# stv_bypass.net
KiCad netlist of a schematic drawn in Altium Designer
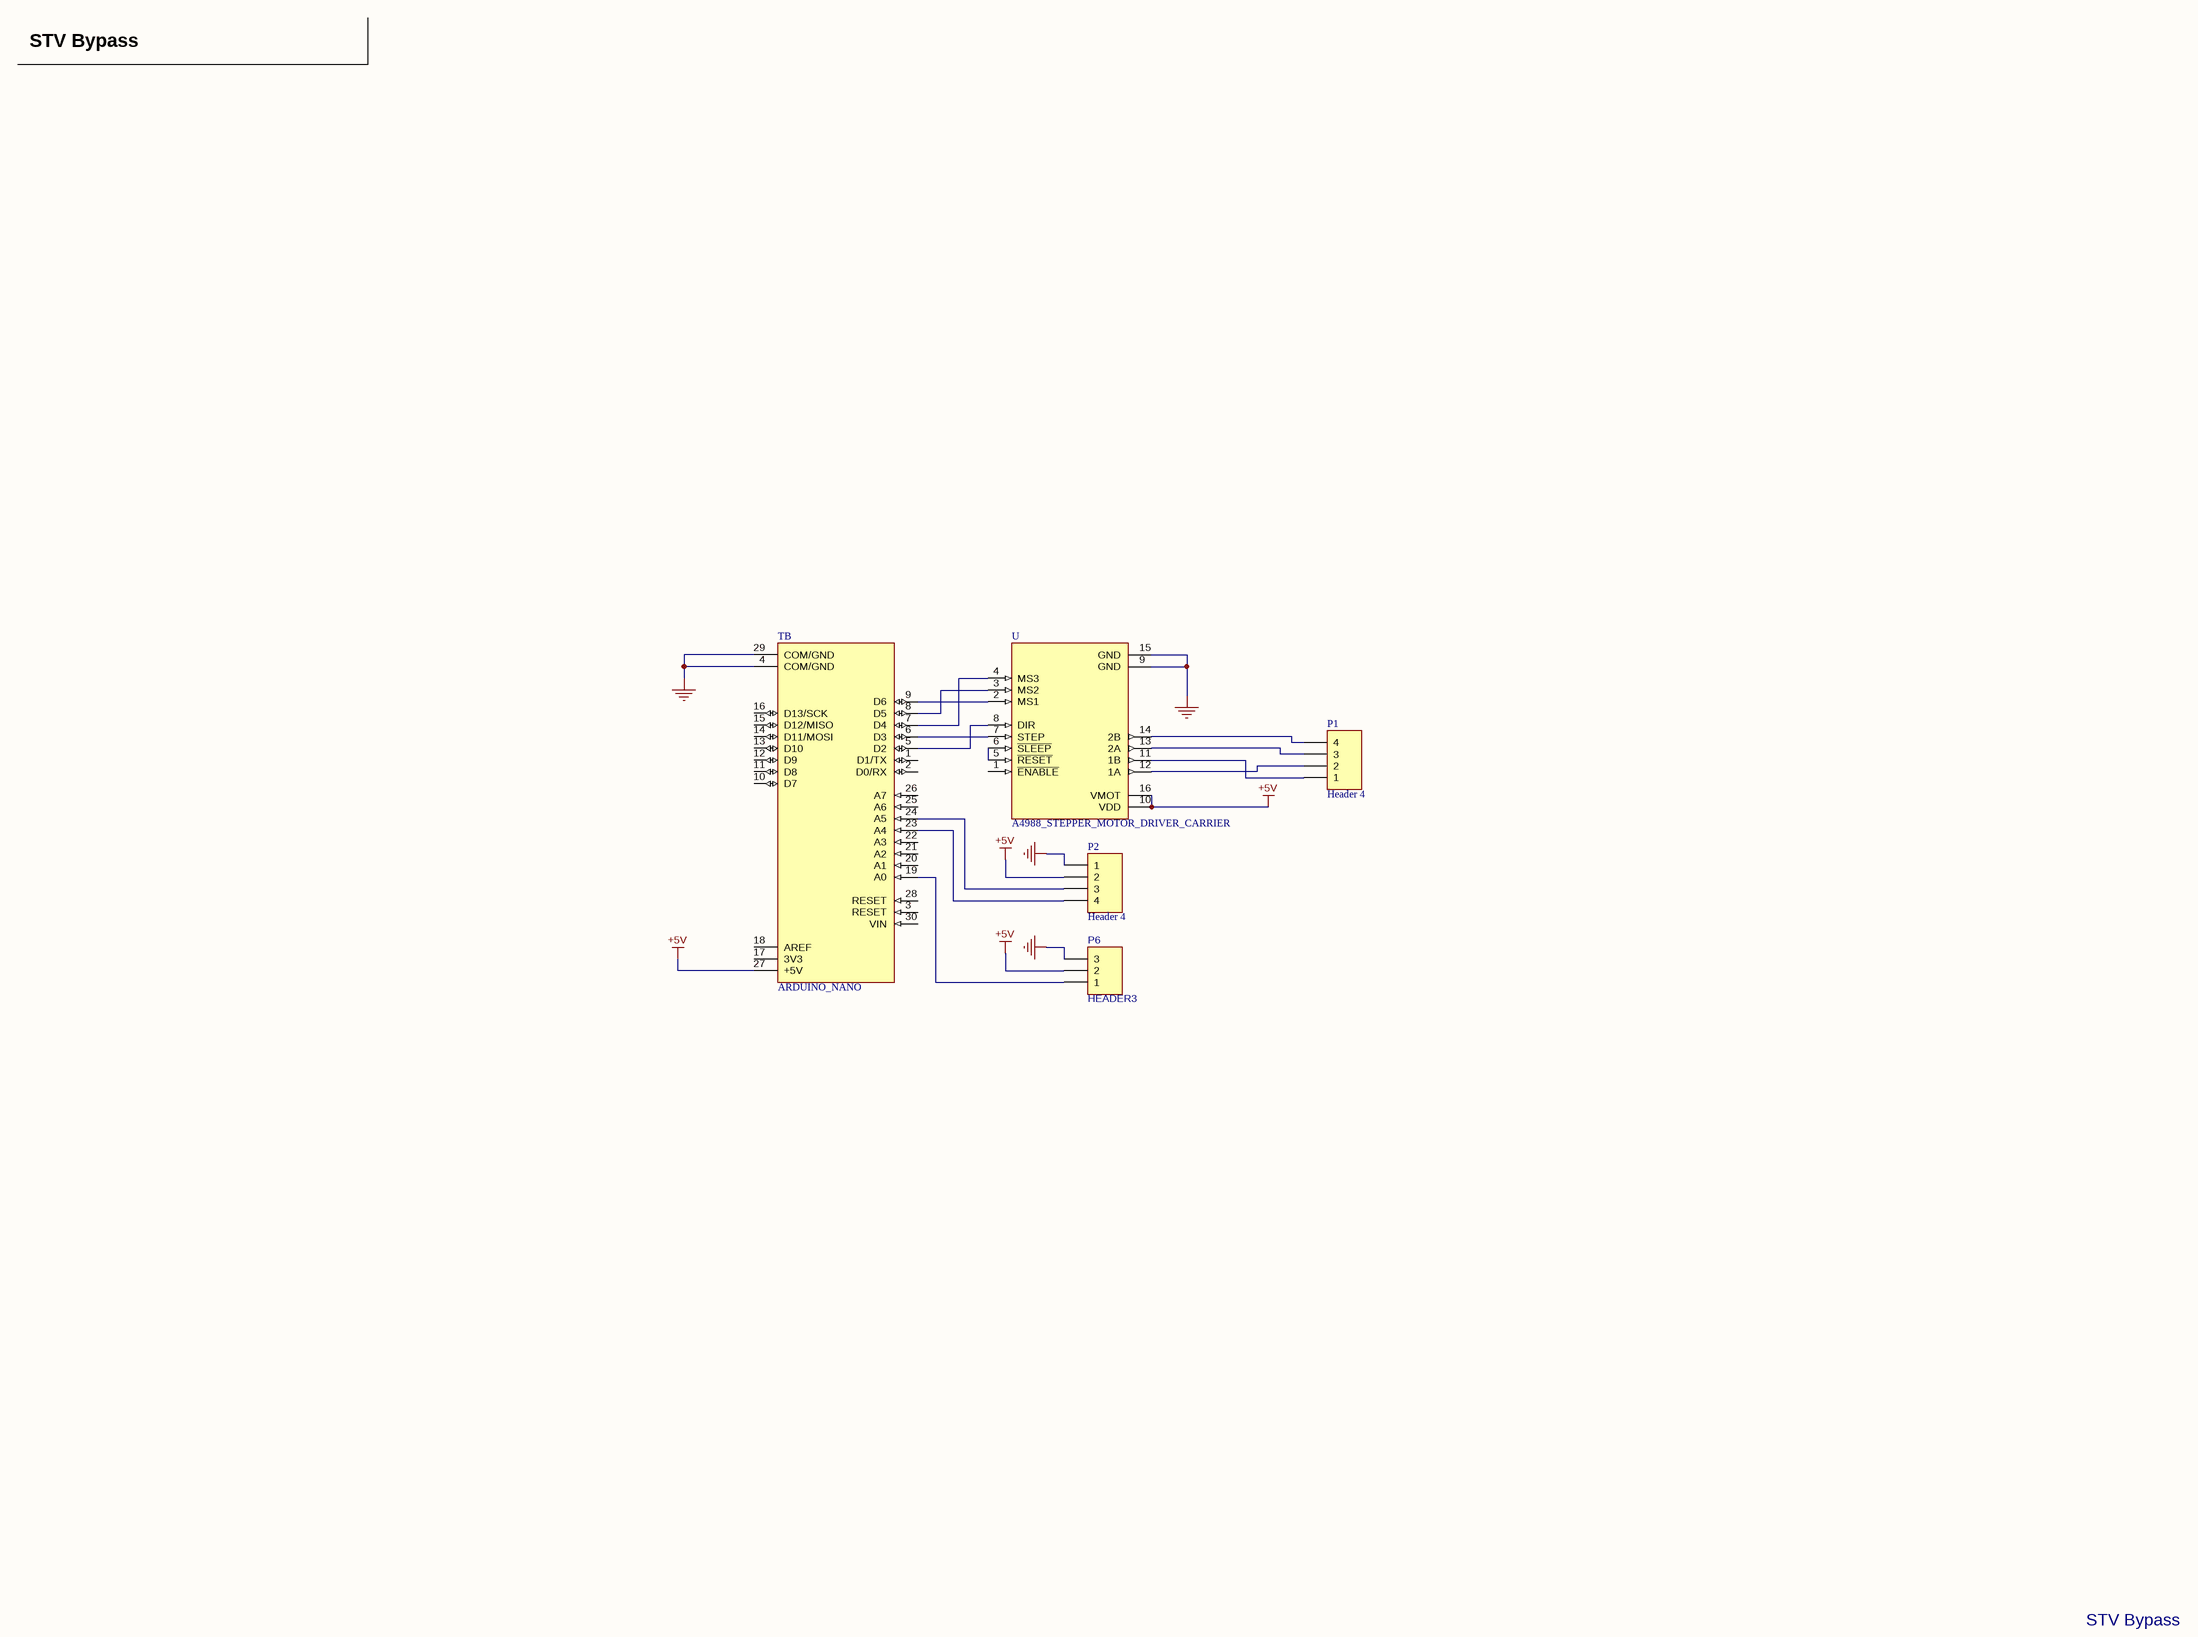
[diagram p0: stv_bypass.SchDoc]

(export (version "E")
  (design (tool "Eeschema 10.0.6"))
  (components
    (comp (ref "P1")
      (value "Header 4")
      (footprint "HDR1X4")
      (description "Header, 4-Pin")
      (fields (field (name "PUBLISHER") "Altium Limited"))
      (libsource (lib "Miscellaneous Connectors") (part "Header 4"))
    )
    (comp (ref "P2")
      (value "Header 4")
      (footprint "HDR1X4")
      (description "Header, 4-Pin")
      (fields (field (name "PUBLISHER") "Altium Limited"))
      (libsource (lib "") (part "Header 4_1"))
    )
    (comp (ref "P6")
      (value "HEADER3")
      (footprint "HDR1X3")
      (description "CONN HEADER MALE 3POS .1\" GOLD")
      (libsource (lib "silverbullet") (part "HEADER-3_1"))
    )
    (comp (ref "TB")
      (value "ARDUINO_NANO")
      (footprint "SnapEDApcb:SHIELD_ARDUINO_NANO")
      (description "ATSAMD21G18A Arduino Nano 33 IoT SAM D ARMÂ® CortexÂ®-M0+ MCU 32-Bit Embedded Evaluation Board")
      (fields (field (name "MP") "ARDUINO NANO") (field (name "MF") "Arduino"))
      (libsource (lib "SnapEDAsch") (part "ARDUINO_NANO"))
    )
    (comp (ref "U")
      (value "A4988_STEPPER_MOTOR_DRIVER_CARRIER")
      (footprint "SnapEDApcb:MODULE_A4988_STEPPER_MOTOR_DRIVER_CARRIER")
      (description "Stepper Motor Driver")
      (fields (field (name "MP") "A4988 STEPPER MOTOR DRIVER CARRIER") (field (name "MF") "Pololu"))
      (libsource (lib "SnapEDAsch") (part "A4988_STEPPER_MOTOR_DRIVER_CARRIER"))
    )
  )
  (nets
    (net (code "1") (name "+5V") (class "Default")
      (node (ref "P2") (pin "2") (pinfunction "2_2") (pintype "passive"))
      (node (ref "P6") (pin "2") (pinfunction "2_2") (pintype "passive"))
      (node (ref "TB") (pin "27") (pinfunction "+5V_27") (pintype "power_in"))
      (node (ref "U") (pin "10") (pinfunction "VDD_10") (pintype "power_in"))
      (node (ref "U") (pin "16") (pinfunction "VMOT_16") (pintype "power_in"))
    )
    (net (code "2") (name "GND") (class "Default")
      (node (ref "P2") (pin "1") (pinfunction "1_1") (pintype "passive"))
      (node (ref "P6") (pin "3") (pinfunction "3_3") (pintype "passive"))
      (node (ref "TB") (pin "29") (pinfunction "COM/GND_29") (pintype "power_in"))
      (node (ref "TB") (pin "4") (pinfunction "COM/GND_4") (pintype "power_in"))
      (node (ref "U") (pin "15") (pinfunction "GND_15") (pintype "power_in"))
      (node (ref "U") (pin "9") (pinfunction "GND_9") (pintype "power_in"))
    )
    (net (code "3") (name "Net-(TB-A0)") (class "Default")
      (node (ref "P6") (pin "1") (pinfunction "1_1") (pintype "passive"))
      (node (ref "TB") (pin "19") (pinfunction "A0_19") (pintype "input"))
    )
    (net (code "4") (name "Net-(TB-A4)") (class "Default")
      (node (ref "P2") (pin "4") (pinfunction "4_4") (pintype "passive"))
      (node (ref "TB") (pin "23") (pinfunction "A4_23") (pintype "input"))
    )
    (net (code "5") (name "Net-(TB-A5)") (class "Default")
      (node (ref "P2") (pin "3") (pinfunction "3_3") (pintype "passive"))
      (node (ref "TB") (pin "24") (pinfunction "A5_24") (pintype "input"))
    )
    (net (code "6") (name "Net-(TB-D2)") (class "Default")
      (node (ref "TB") (pin "5") (pinfunction "D2_5") (pintype "bidirectional"))
      (node (ref "U") (pin "8") (pinfunction "DIR_8") (pintype "input"))
    )
    (net (code "7") (name "Net-(TB-D3)") (class "Default")
      (node (ref "TB") (pin "6") (pinfunction "D3_6") (pintype "bidirectional"))
      (node (ref "U") (pin "7") (pinfunction "STEP_7") (pintype "input"))
    )
    (net (code "8") (name "Net-(TB-D4)") (class "Default")
      (node (ref "TB") (pin "7") (pinfunction "D4_7") (pintype "bidirectional"))
      (node (ref "U") (pin "4") (pinfunction "MS3_4") (pintype "input"))
    )
    (net (code "9") (name "Net-(TB-D5)") (class "Default")
      (node (ref "TB") (pin "8") (pinfunction "D5_8") (pintype "bidirectional"))
      (node (ref "U") (pin "3") (pinfunction "MS2_3") (pintype "input"))
    )
    (net (code "10") (name "Net-(TB-D6)") (class "Default")
      (node (ref "TB") (pin "9") (pinfunction "D6_9") (pintype "bidirectional"))
      (node (ref "U") (pin "2") (pinfunction "MS1_2") (pintype "input"))
    )
    (net (code "11") (name "Net-(U-1A)") (class "Default")
      (node (ref "P1") (pin "2") (pinfunction "2_2") (pintype "passive"))
      (node (ref "U") (pin "12") (pinfunction "1A_12") (pintype "output"))
    )
    (net (code "12") (name "Net-(U-1B)") (class "Default")
      (node (ref "P1") (pin "1") (pinfunction "1_1") (pintype "passive"))
      (node (ref "U") (pin "11") (pinfunction "1B_11") (pintype "output"))
    )
    (net (code "13") (name "Net-(U-2A)") (class "Default")
      (node (ref "P1") (pin "3") (pinfunction "3_3") (pintype "passive"))
      (node (ref "U") (pin "13") (pinfunction "2A_13") (pintype "output"))
    )
    (net (code "14") (name "Net-(U-2B)") (class "Default")
      (node (ref "P1") (pin "4") (pinfunction "4_4") (pintype "passive"))
      (node (ref "U") (pin "14") (pinfunction "2B_14") (pintype "output"))
    )
    (net (code "15") (name "Net-(U-~{RESET})") (class "Default")
      (node (ref "U") (pin "5") (pinfunction "~{RESET}_5") (pintype "input"))
      (node (ref "U") (pin "6") (pinfunction "~{SLEEP}_6") (pintype "input"))
    )
    (net (code "16") (name "unconnected-(TB-3V3-Pad17)") (class "Default")
      (node (ref "TB") (pin "17") (pinfunction "3V3_17") (pintype "power_in"))
    )
    (net (code "17") (name "unconnected-(TB-A1-Pad20)") (class "Default")
      (node (ref "TB") (pin "20") (pinfunction "A1_20") (pintype "input"))
    )
    (net (code "18") (name "unconnected-(TB-A2-Pad21)") (class "Default")
      (node (ref "TB") (pin "21") (pinfunction "A2_21") (pintype "input"))
    )
    (net (code "19") (name "unconnected-(TB-A3-Pad22)") (class "Default")
      (node (ref "TB") (pin "22") (pinfunction "A3_22") (pintype "input"))
    )
    (net (code "20") (name "unconnected-(TB-A6-Pad25)") (class "Default")
      (node (ref "TB") (pin "25") (pinfunction "A6_25") (pintype "input"))
    )
    (net (code "21") (name "unconnected-(TB-A7-Pad26)") (class "Default")
      (node (ref "TB") (pin "26") (pinfunction "A7_26") (pintype "input"))
    )
    (net (code "22") (name "unconnected-(TB-AREF-Pad18)") (class "Default")
      (node (ref "TB") (pin "18") (pinfunction "AREF_18") (pintype "power_in"))
    )
    (net (code "23") (name "unconnected-(TB-D0{slash}RX-Pad2)") (class "Default")
      (node (ref "TB") (pin "2") (pinfunction "D0/RX_2") (pintype "bidirectional"))
    )
    (net (code "24") (name "unconnected-(TB-D1{slash}TX-Pad1)") (class "Default")
      (node (ref "TB") (pin "1") (pinfunction "D1/TX_1") (pintype "bidirectional"))
    )
    (net (code "25") (name "unconnected-(TB-D7-Pad10)") (class "Default")
      (node (ref "TB") (pin "10") (pinfunction "D7_10") (pintype "bidirectional"))
    )
    (net (code "26") (name "unconnected-(TB-D8-Pad11)") (class "Default")
      (node (ref "TB") (pin "11") (pinfunction "D8_11") (pintype "bidirectional"))
    )
    (net (code "27") (name "unconnected-(TB-D9-Pad12)") (class "Default")
      (node (ref "TB") (pin "12") (pinfunction "D9_12") (pintype "bidirectional"))
    )
    (net (code "28") (name "unconnected-(TB-D10-Pad13)") (class "Default")
      (node (ref "TB") (pin "13") (pinfunction "D10_13") (pintype "bidirectional"))
    )
    (net (code "29") (name "unconnected-(TB-D11{slash}MOSI-Pad14)") (class "Default")
      (node (ref "TB") (pin "14") (pinfunction "D11/MOSI_14") (pintype "bidirectional"))
    )
    (net (code "30") (name "unconnected-(TB-D12{slash}MISO-Pad15)") (class "Default")
      (node (ref "TB") (pin "15") (pinfunction "D12/MISO_15") (pintype "bidirectional"))
    )
    (net (code "31") (name "unconnected-(TB-D13{slash}SCK-Pad16)") (class "Default")
      (node (ref "TB") (pin "16") (pinfunction "D13/SCK_16") (pintype "bidirectional"))
    )
    (net (code "32") (name "unconnected-(TB-RESET-Pad3)") (class "Default")
      (node (ref "TB") (pin "3") (pinfunction "RESET_3") (pintype "input"))
    )
    (net (code "33") (name "unconnected-(TB-RESET-Pad28)") (class "Default")
      (node (ref "TB") (pin "28") (pinfunction "RESET_28") (pintype "input"))
    )
    (net (code "34") (name "unconnected-(TB-VIN-Pad30)") (class "Default")
      (node (ref "TB") (pin "30") (pinfunction "VIN_30") (pintype "input"))
    )
    (net (code "35") (name "unconnected-(U-~{ENABLE}-Pad1)") (class "Default")
      (node (ref "U") (pin "1") (pinfunction "~{ENABLE}_1") (pintype "input"))
    )
  )
)
